# VESC_KS75600_motor_mcu.net
KiCad netlist of a schematic drawn in Altium Designer
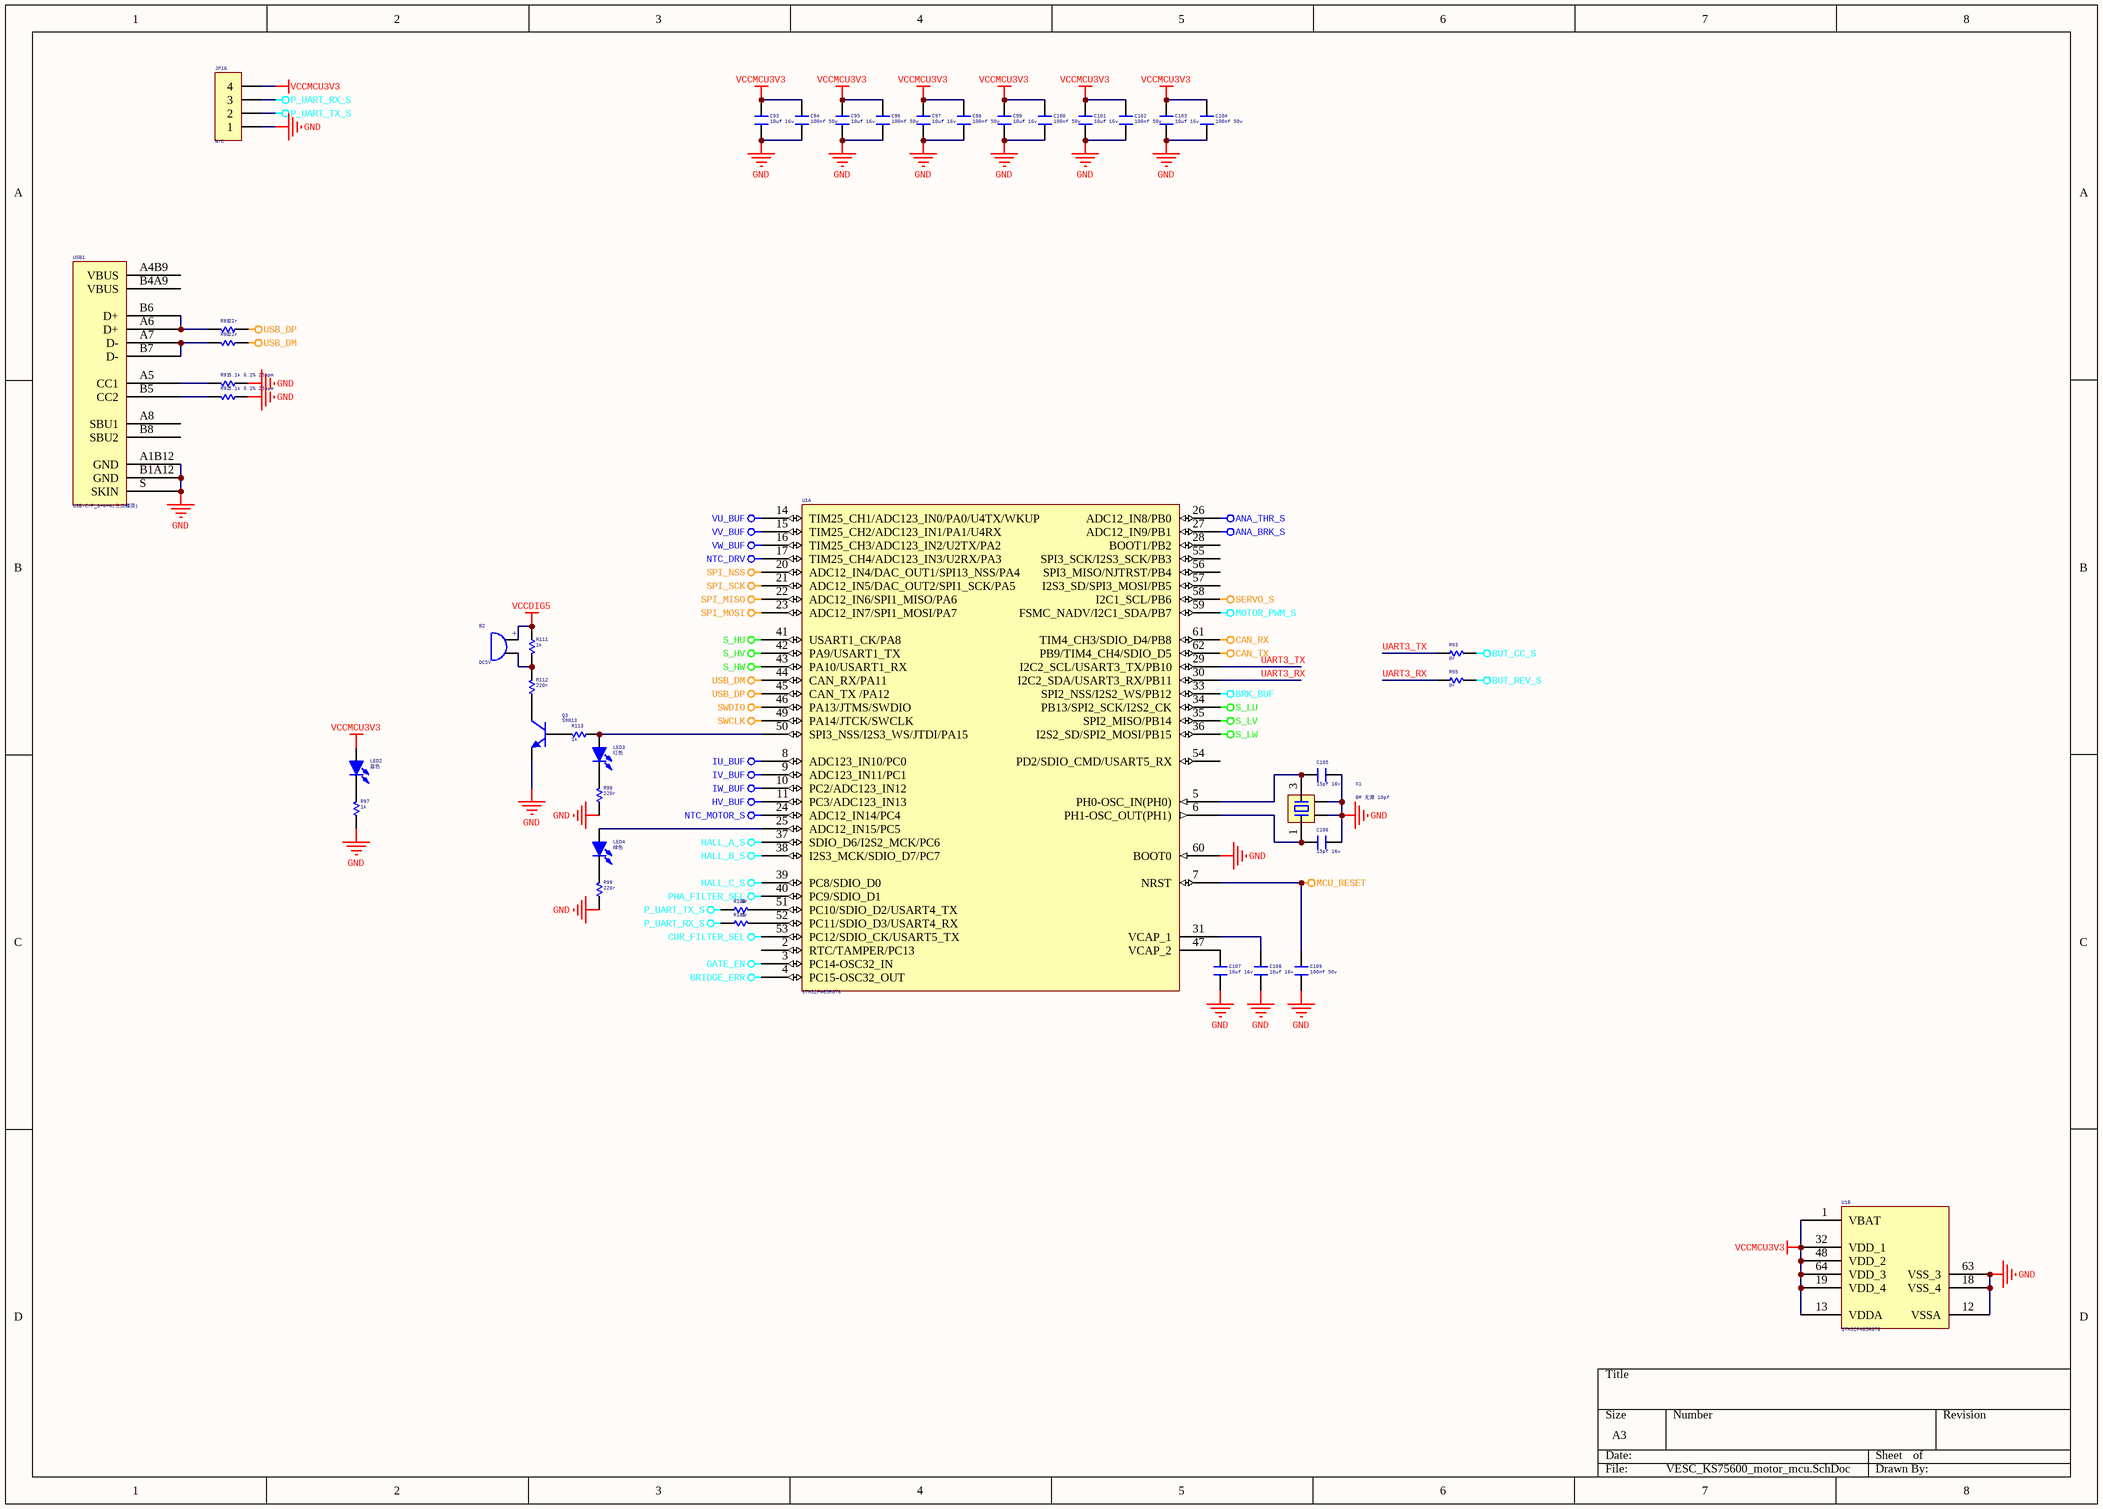
[diagram p0: VESC_KS75600_motor_mcu.SchDoc]

(export (version "E")
  (design (tool "Eeschema 10.0.6"))
  (components
    (comp (ref "B2")
      (value "DC5V")
      (footprint "BEEP 5x9x5.5")
      (description "蜂鸣器")
      (libsource (lib "未分类器件") (part "BEEP"))
    )
    (comp (ref "C93")
      (value "10uf 16v")
      (footprint "C 0805")
      (description "无极性贴片电容")
      (fields (field (name "VOLTAGE") "16v"))
      (libsource (lib "电阻-电容-电感") (part "C"))
    )
    (comp (ref "C94")
      (value "100nf 50v")
      (footprint "C 0603")
      (description "无极性贴片电容")
      (fields (field (name "VOLTAGE") "50v"))
      (libsource (lib "电阻-电容-电感") (part "C"))
    )
    (comp (ref "C95")
      (value "10uf 16v")
      (footprint "C 0805")
      (description "无极性贴片电容")
      (fields (field (name "VOLTAGE") "16v"))
      (libsource (lib "电阻-电容-电感") (part "C"))
    )
    (comp (ref "C96")
      (value "100nf 50v")
      (footprint "C 0603")
      (description "无极性贴片电容")
      (fields (field (name "VOLTAGE") "50v"))
      (libsource (lib "电阻-电容-电感") (part "C"))
    )
    (comp (ref "C97")
      (value "10uf 16v")
      (footprint "C 0805")
      (description "无极性贴片电容")
      (fields (field (name "VOLTAGE") "16v"))
      (libsource (lib "电阻-电容-电感") (part "C"))
    )
    (comp (ref "C98")
      (value "100nf 50v")
      (footprint "C 0603")
      (description "无极性贴片电容")
      (fields (field (name "VOLTAGE") "50v"))
      (libsource (lib "电阻-电容-电感") (part "C"))
    )
    (comp (ref "C99")
      (value "10uf 16v")
      (footprint "C 0805")
      (description "无极性贴片电容")
      (fields (field (name "VOLTAGE") "16v"))
      (libsource (lib "电阻-电容-电感") (part "C"))
    )
    (comp (ref "C100")
      (value "100nf 50v")
      (footprint "C 0603")
      (description "无极性贴片电容")
      (fields (field (name "VOLTAGE") "50v"))
      (libsource (lib "电阻-电容-电感") (part "C"))
    )
    (comp (ref "C101")
      (value "10uf 16v")
      (footprint "C 0805")
      (description "无极性贴片电容")
      (fields (field (name "VOLTAGE") "16v"))
      (libsource (lib "电阻-电容-电感") (part "C"))
    )
    (comp (ref "C102")
      (value "100nf 50v")
      (footprint "C 0603")
      (description "无极性贴片电容")
      (fields (field (name "VOLTAGE") "50v"))
      (libsource (lib "电阻-电容-电感") (part "C"))
    )
    (comp (ref "C103")
      (value "10uf 16v")
      (footprint "C 0805")
      (description "无极性贴片电容")
      (fields (field (name "VOLTAGE") "16v"))
      (libsource (lib "电阻-电容-电感") (part "C"))
    )
    (comp (ref "C104")
      (value "100nf 50v")
      (footprint "C 0603")
      (description "无极性贴片电容")
      (fields (field (name "VOLTAGE") "50v"))
      (libsource (lib "电阻-电容-电感") (part "C"))
    )
    (comp (ref "C105")
      (value "15pf 16v")
      (footprint "C 0603")
      (description "无极性贴片电容")
      (fields (field (name "VOLTAGE") "16v"))
      (libsource (lib "电阻-电容-电感") (part "C"))
    )
    (comp (ref "C106")
      (value "15pf 16v")
      (footprint "C 0603")
      (description "无极性贴片电容")
      (fields (field (name "VOLTAGE") "16v"))
      (libsource (lib "电阻-电容-电感") (part "C"))
    )
    (comp (ref "C107")
      (value "10uf 16v")
      (footprint "C 0805")
      (description "无极性贴片电容")
      (fields (field (name "VOLTAGE") "16v"))
      (libsource (lib "电阻-电容-电感") (part "C"))
    )
    (comp (ref "C108")
      (value "10uf 16v")
      (footprint "C 0805")
      (description "无极性贴片电容")
      (fields (field (name "VOLTAGE") "16v"))
      (libsource (lib "电阻-电容-电感") (part "C"))
    )
    (comp (ref "C109")
      (value "100nf 50v")
      (footprint "C 0603")
      (description "无极性贴片电容")
      (fields (field (name "VOLTAGE") "50v"))
      (libsource (lib "电阻-电容-电感") (part "C"))
    )
    (comp (ref "JP16")
      (value "N/C")
      (footprint "HDR-1X4")
      (description "4P接插件")
      (libsource (lib "接插件") (part "Header 4"))
    )
    (comp (ref "LED2")
      (value "蓝色")
      (footprint "LED 0603G")
      (description "贴片LED")
      (libsource (lib "LED") (part "LED-SMD"))
    )
    (comp (ref "LED3")
      (value "红色")
      (footprint "LED 0603G")
      (description "贴片LED")
      (libsource (lib "LED") (part "LED-SMD"))
    )
    (comp (ref "LED4")
      (value "绿色")
      (footprint "LED 0603G")
      (description "贴片LED")
      (libsource (lib "LED") (part "LED-SMD"))
    )
    (comp (ref "Q3")
      (value "S9013")
      (footprint "SOT23-3N")
      (description "低频放大-NPN型")
      (libsource (lib "三极管") (part "9013-SMD"))
    )
    (comp (ref "R89")
      (value "22r")
      (footprint "R 0603")
      (description "贴片电阻")
      (libsource (lib "电阻-电容-电感") (part "R"))
    )
    (comp (ref "R90")
      (value "22r")
      (footprint "R 0603")
      (description "贴片电阻")
      (libsource (lib "电阻-电容-电感") (part "R"))
    )
    (comp (ref "R91")
      (value "5.1k 0.1% 25ppm")
      (footprint "R 0805-HP")
      (description "贴片电阻")
      (libsource (lib "电阻-电容-电感") (part "R"))
    )
    (comp (ref "R92")
      (value "5.1k 0.1% 25ppm")
      (footprint "R 0805-HP")
      (description "贴片电阻")
      (libsource (lib "电阻-电容-电感") (part "R"))
    )
    (comp (ref "R93")
      (value "0r")
      (footprint "R 0603")
      (description "贴片电阻")
      (libsource (lib "电阻-电容-电感") (part "R"))
    )
    (comp (ref "R95")
      (value "0r")
      (footprint "R 0603")
      (description "贴片电阻")
      (libsource (lib "电阻-电容-电感") (part "R"))
    )
    (comp (ref "R97")
      (value "1k")
      (footprint "R 0603")
      (description "贴片电阻")
      (libsource (lib "电阻-电容-电感") (part "R"))
    )
    (comp (ref "R98")
      (value "220r")
      (footprint "R 0603")
      (description "贴片电阻")
      (libsource (lib "电阻-电容-电感") (part "R"))
    )
    (comp (ref "R99")
      (value "220r")
      (footprint "R 0603")
      (description "贴片电阻")
      (libsource (lib "电阻-电容-电感") (part "R"))
    )
    (comp (ref "R100")
      (value "0r")
      (footprint "R 0603")
      (description "贴片电阻")
      (libsource (lib "电阻-电容-电感") (part "R"))
    )
    (comp (ref "R101")
      (value "0r")
      (footprint "R 0603")
      (description "贴片电阻")
      (libsource (lib "电阻-电容-电感") (part "R"))
    )
    (comp (ref "R111")
      (value "1k")
      (footprint "R 0603")
      (description "贴片电阻")
      (libsource (lib "电阻-电容-电感") (part "R"))
    )
    (comp (ref "R112")
      (value "220r")
      (footprint "R 0603")
      (description "贴片电阻")
      (libsource (lib "电阻-电容-电感") (part "R"))
    )
    (comp (ref "R113")
      (value "1k")
      (footprint "R 0603")
      (description "贴片电阻")
      (libsource (lib "电阻-电容-电感") (part "R"))
    )
    (comp (ref "U1")
      (value "STM32F405RGT6")
      (footprint "LQFP64 10x10_L")
      (description "Flash:1024/RAM:192/IO:51")
      (libsource (lib "STM32系列单片机") (part "STM32F405RG"))
    )
    (comp (ref "USB1")
      (value "USB-C/P_8+4+4(三次模顶)")
      (footprint "USB-C/S_16_0D_F")
      (description "USB-C型贴片母接口 8（8线）+4 (电源) + 4（外壳）（2.0基础数据+CC+SBU）")
      (libsource (lib "接口类") (part "USB-C/P_8+4+4"))
    )
    (comp (ref "X1")
      (value "8M 无源 10pf")
      (footprint "XTAL-3225")
      (description "4脚晶振")
      (libsource (lib "保险丝-晶振") (part "XTAL-4"))
    )
  )
  (nets
    (net (code "1") (name "/UART3_RX") (class "Default")
      (node (ref "R95") (pin "1") (pinfunction "1_1") (pintype "passive"))
      (node (ref "U1") (pin "30") (pinfunction "I2C2_SDA/USART3_RX/PB11_30") (pintype "bidirectional"))
    )
    (net (code "2") (name "/UART3_TX") (class "Default")
      (node (ref "R93") (pin "1") (pinfunction "1_1") (pintype "passive"))
      (node (ref "U1") (pin "29") (pinfunction "I2C2_SCL/USART3_TX/PB10_29") (pintype "bidirectional"))
    )
    (net (code "3") (name "ANA_BRK_S") (class "Default")
      (node (ref "U1") (pin "27") (pinfunction "ADC12_IN9/PB1_27") (pintype "bidirectional"))
    )
    (net (code "4") (name "ANA_THR_S") (class "Default")
      (node (ref "U1") (pin "26") (pinfunction "ADC12_IN8/PB0_26") (pintype "bidirectional"))
    )
    (net (code "5") (name "BRIDGE_ERR") (class "Default")
      (node (ref "U1") (pin "4") (pinfunction "PC15-OSC32_OUT_4") (pintype "bidirectional"))
    )
    (net (code "6") (name "BRK_BUF") (class "Default")
      (node (ref "U1") (pin "33") (pinfunction "SPI2_NSS/I2S2_WS/PB12_33") (pintype "bidirectional"))
    )
    (net (code "7") (name "BUT_CC_S") (class "Default")
      (node (ref "R93") (pin "2") (pinfunction "2_2") (pintype "passive"))
    )
    (net (code "8") (name "BUT_REV_S") (class "Default")
      (node (ref "R95") (pin "2") (pinfunction "2_2") (pintype "passive"))
    )
    (net (code "9") (name "CAN_RX") (class "Default")
      (node (ref "U1") (pin "61") (pinfunction "TIM4_CH3/SDIO_D4/PB8_61") (pintype "bidirectional"))
    )
    (net (code "10") (name "CAN_TX") (class "Default")
      (node (ref "U1") (pin "62") (pinfunction "PB9/TIM4_CH4/SDIO_D5_62") (pintype "bidirectional"))
    )
    (net (code "11") (name "CUR_FILTER_SEL") (class "Default")
      (node (ref "U1") (pin "53") (pinfunction "PC12/SDIO_CK/USART5_TX_53") (pintype "bidirectional"))
    )
    (net (code "12") (name "GATE_EN") (class "Default")
      (node (ref "U1") (pin "3") (pinfunction "PC14-OSC32_IN_3") (pintype "bidirectional"))
    )
    (net (code "13") (name "GND") (class "Default")
      (node (ref "C100") (pin "2") (pinfunction "2_2") (pintype "passive"))
      (node (ref "C101") (pin "2") (pinfunction "2_2") (pintype "passive"))
      (node (ref "C102") (pin "2") (pinfunction "2_2") (pintype "passive"))
      (node (ref "C103") (pin "2") (pinfunction "2_2") (pintype "passive"))
      (node (ref "C104") (pin "2") (pinfunction "2_2") (pintype "passive"))
      (node (ref "C105") (pin "1") (pinfunction "1_1") (pintype "passive"))
      (node (ref "C106") (pin "1") (pinfunction "1_1") (pintype "passive"))
      (node (ref "C107") (pin "2") (pinfunction "2_2") (pintype "passive"))
      (node (ref "C108") (pin "2") (pinfunction "2_2") (pintype "passive"))
      (node (ref "C109") (pin "1") (pinfunction "1_1") (pintype "passive"))
      (node (ref "C93") (pin "2") (pinfunction "2_2") (pintype "passive"))
      (node (ref "C94") (pin "2") (pinfunction "2_2") (pintype "passive"))
      (node (ref "C95") (pin "2") (pinfunction "2_2") (pintype "passive"))
      (node (ref "C96") (pin "2") (pinfunction "2_2") (pintype "passive"))
      (node (ref "C97") (pin "2") (pinfunction "2_2") (pintype "passive"))
      (node (ref "C98") (pin "2") (pinfunction "2_2") (pintype "passive"))
      (node (ref "C99") (pin "2") (pinfunction "2_2") (pintype "passive"))
      (node (ref "JP16") (pin "1") (pinfunction "1_1") (pintype "passive"))
      (node (ref "Q3") (pin "2") (pinfunction "E_2") (pintype "passive"))
      (node (ref "R91") (pin "1") (pinfunction "1_1") (pintype "passive"))
      (node (ref "R92") (pin "1") (pinfunction "1_1") (pintype "passive"))
      (node (ref "R97") (pin "1") (pinfunction "1_1") (pintype "passive"))
      (node (ref "R98") (pin "1") (pinfunction "1_1") (pintype "passive"))
      (node (ref "R99") (pin "1") (pinfunction "1_1") (pintype "passive"))
      (node (ref "U1") (pin "12") (pinfunction "VSSA_12") (pintype "power_in"))
      (node (ref "U1") (pin "18") (pinfunction "VSS_4_18") (pintype "power_in"))
      (node (ref "U1") (pin "60") (pinfunction "BOOT0_60") (pintype "input"))
      (node (ref "U1") (pin "63") (pinfunction "VSS_3_63") (pintype "power_in"))
      (node (ref "USB1") (pin "A1B12") (pinfunction "GND_A1B12") (pintype "passive"))
      (node (ref "USB1") (pin "B1A12") (pinfunction "GND_B1A12") (pintype "passive"))
      (node (ref "USB1") (pin "S") (pinfunction "SKIN_S") (pintype "passive"))
      (node (ref "X1") (pin "2") (pinfunction "2_2") (pintype "passive"))
      (node (ref "X1") (pin "4") (pinfunction "4_4") (pintype "passive"))
    )
    (net (code "14") (name "HALL_A_S") (class "Default")
      (node (ref "U1") (pin "37") (pinfunction "SDIO_D6/I2S2_MCK/PC6_37") (pintype "bidirectional"))
    )
    (net (code "15") (name "HALL_B_S") (class "Default")
      (node (ref "U1") (pin "38") (pinfunction "I2S3_MCK/SDIO_D7/PC7_38") (pintype "bidirectional"))
    )
    (net (code "16") (name "HALL_C_S") (class "Default")
      (node (ref "U1") (pin "39") (pinfunction "PC8/SDIO_D0_39") (pintype "bidirectional"))
    )
    (net (code "17") (name "HV_BUF") (class "Default")
      (node (ref "U1") (pin "11") (pinfunction "PC3/ADC123_IN13_11") (pintype "bidirectional"))
    )
    (net (code "18") (name "IU_BUF") (class "Default")
      (node (ref "U1") (pin "8") (pinfunction "ADC123_IN10/PC0_8") (pintype "bidirectional"))
    )
    (net (code "19") (name "IV_BUF") (class "Default")
      (node (ref "U1") (pin "9") (pinfunction "ADC123_IN11/PC1_9") (pintype "bidirectional"))
    )
    (net (code "20") (name "IW_BUF") (class "Default")
      (node (ref "U1") (pin "10") (pinfunction "PC2/ADC123_IN12_10") (pintype "bidirectional"))
    )
    (net (code "21") (name "MCU_RESET") (class "Default")
      (node (ref "C109") (pin "2") (pinfunction "2_2") (pintype "passive"))
      (node (ref "U1") (pin "7") (pinfunction "NRST_7") (pintype "bidirectional"))
    )
    (net (code "22") (name "MOTOR_PWM_S") (class "Default")
      (node (ref "U1") (pin "59") (pinfunction "FSMC_NADV/I2C1_SDA/PB7_59") (pintype "bidirectional"))
    )
    (net (code "23") (name "NTC_DRV") (class "Default")
      (node (ref "U1") (pin "17") (pinfunction "TIM25_CH4/ADC123_IN3/U2RX/PA3_17") (pintype "bidirectional"))
    )
    (net (code "24") (name "NTC_MOTOR_S") (class "Default")
      (node (ref "U1") (pin "24") (pinfunction "ADC12_IN14/PC4_24") (pintype "bidirectional"))
    )
    (net (code "25") (name "Net-(B2-Pad2)") (class "Default")
      (node (ref "B2") (pin "2") (pinfunction "2_2") (pintype "passive"))
      (node (ref "R111") (pin "2") (pinfunction "2_2") (pintype "passive"))
      (node (ref "R112") (pin "2") (pinfunction "2_2") (pintype "passive"))
    )
    (net (code "26") (name "Net-(LED2-K)") (class "Default")
      (node (ref "LED2") (pin "2") (pinfunction "K_2") (pintype "passive"))
      (node (ref "R97") (pin "2") (pinfunction "2_2") (pintype "passive"))
    )
    (net (code "27") (name "Net-(LED3-A)") (class "Default")
      (node (ref "LED3") (pin "1") (pinfunction "A_1") (pintype "passive"))
      (node (ref "R113") (pin "1") (pinfunction "1_1") (pintype "passive"))
      (node (ref "U1") (pin "50") (pinfunction "SPI3_NSS/I2S3_WS/JTDI/PA15_50") (pintype "bidirectional"))
    )
    (net (code "28") (name "Net-(LED3-K)") (class "Default")
      (node (ref "LED3") (pin "2") (pinfunction "K_2") (pintype "passive"))
      (node (ref "R98") (pin "2") (pinfunction "2_2") (pintype "passive"))
    )
    (net (code "29") (name "Net-(LED4-A)") (class "Default")
      (node (ref "LED4") (pin "1") (pinfunction "A_1") (pintype "passive"))
      (node (ref "U1") (pin "25") (pinfunction "ADC12_IN15/PC5_25") (pintype "bidirectional"))
    )
    (net (code "30") (name "Net-(LED4-K)") (class "Default")
      (node (ref "LED4") (pin "2") (pinfunction "K_2") (pintype "passive"))
      (node (ref "R99") (pin "2") (pinfunction "2_2") (pintype "passive"))
    )
    (net (code "31") (name "Net-(Q3-B)") (class "Default")
      (node (ref "Q3") (pin "1") (pinfunction "B_1") (pintype "passive"))
      (node (ref "R113") (pin "2") (pinfunction "2_2") (pintype "passive"))
    )
    (net (code "32") (name "Net-(Q3-C)") (class "Default")
      (node (ref "Q3") (pin "3") (pinfunction "C_3") (pintype "passive"))
      (node (ref "R112") (pin "1") (pinfunction "1_1") (pintype "passive"))
    )
    (net (code "33") (name "Net-(R89-Pad2)") (class "Default")
      (node (ref "R89") (pin "2") (pinfunction "2_2") (pintype "passive"))
      (node (ref "USB1") (pin "A6") (pinfunction "D+_A6") (pintype "passive"))
      (node (ref "USB1") (pin "B6") (pinfunction "D+_B6") (pintype "passive"))
    )
    (net (code "34") (name "Net-(R90-Pad2)") (class "Default")
      (node (ref "R90") (pin "2") (pinfunction "2_2") (pintype "passive"))
      (node (ref "USB1") (pin "A7") (pinfunction "D-_A7") (pintype "passive"))
      (node (ref "USB1") (pin "B7") (pinfunction "D-_B7") (pintype "passive"))
    )
    (net (code "35") (name "Net-(U1A-PC10{slash}SDIO_D2{slash}USART4_TX)") (class "Default")
      (node (ref "R100") (pin "2") (pinfunction "2_2") (pintype "passive"))
      (node (ref "U1") (pin "51") (pinfunction "PC10/SDIO_D2/USART4_TX_51") (pintype "bidirectional"))
    )
    (net (code "36") (name "Net-(U1A-PC11{slash}SDIO_D3{slash}USART4_RX)") (class "Default")
      (node (ref "R101") (pin "2") (pinfunction "2_2") (pintype "passive"))
      (node (ref "U1") (pin "52") (pinfunction "PC11/SDIO_D3/USART4_RX_52") (pintype "bidirectional"))
    )
    (net (code "37") (name "Net-(U1A-PH0-OSC_IN(PH0))") (class "Default")
      (node (ref "C105") (pin "2") (pinfunction "2_2") (pintype "passive"))
      (node (ref "U1") (pin "5") (pinfunction "PH0-OSC_IN(PH0)_5") (pintype "input"))
      (node (ref "X1") (pin "3") (pinfunction "3_3") (pintype "passive"))
    )
    (net (code "38") (name "Net-(U1A-PH1-OSC_OUT(PH1))") (class "Default")
      (node (ref "C106") (pin "2") (pinfunction "2_2") (pintype "passive"))
      (node (ref "U1") (pin "6") (pinfunction "PH1-OSC_OUT(PH1)_6") (pintype "output"))
      (node (ref "X1") (pin "1") (pinfunction "1_1") (pintype "passive"))
    )
    (net (code "39") (name "Net-(U1A-VCAP_1)") (class "Default")
      (node (ref "C108") (pin "1") (pinfunction "1_1") (pintype "passive"))
      (node (ref "U1") (pin "31") (pinfunction "VCAP_1_31") (pintype "passive"))
    )
    (net (code "40") (name "Net-(U1A-VCAP_2)") (class "Default")
      (node (ref "C107") (pin "1") (pinfunction "1_1") (pintype "passive"))
      (node (ref "U1") (pin "47") (pinfunction "VCAP_2_47") (pintype "passive"))
    )
    (net (code "41") (name "Net-(USB1-CC1)") (class "Default")
      (node (ref "R91") (pin "2") (pinfunction "2_2") (pintype "passive"))
      (node (ref "USB1") (pin "A5") (pinfunction "CC1_A5") (pintype "passive"))
    )
    (net (code "42") (name "Net-(USB1-CC2)") (class "Default")
      (node (ref "R92") (pin "2") (pinfunction "2_2") (pintype "passive"))
      (node (ref "USB1") (pin "B5") (pinfunction "CC2_B5") (pintype "passive"))
    )
    (net (code "43") (name "PHA_FILTER_SEL") (class "Default")
      (node (ref "U1") (pin "40") (pinfunction "PC9/SDIO_D1_40") (pintype "bidirectional"))
    )
    (net (code "44") (name "P_UART_RX_S") (class "Default")
      (node (ref "JP16") (pin "3") (pinfunction "3_3") (pintype "passive"))
      (node (ref "R101") (pin "1") (pinfunction "1_1") (pintype "passive"))
    )
    (net (code "45") (name "P_UART_TX_S") (class "Default")
      (node (ref "JP16") (pin "2") (pinfunction "2_2") (pintype "passive"))
      (node (ref "R100") (pin "1") (pinfunction "1_1") (pintype "passive"))
    )
    (net (code "46") (name "SERVO_S") (class "Default")
      (node (ref "U1") (pin "58") (pinfunction "I2C1_SCL/PB6_58") (pintype "bidirectional"))
    )
    (net (code "47") (name "SPI_MISO") (class "Default")
      (node (ref "U1") (pin "22") (pinfunction "ADC12_IN6/SPI1_MISO/PA6_22") (pintype "bidirectional"))
    )
    (net (code "48") (name "SPI_MOSI") (class "Default")
      (node (ref "U1") (pin "23") (pinfunction "ADC12_IN7/SPI1_MOSI/PA7_23") (pintype "bidirectional"))
    )
    (net (code "49") (name "SPI_NSS") (class "Default")
      (node (ref "U1") (pin "20") (pinfunction "ADC12_IN4/DAC_OUT1/SPI13_NSS/PA4_20") (pintype "bidirectional"))
    )
    (net (code "50") (name "SPI_SCK") (class "Default")
      (node (ref "U1") (pin "21") (pinfunction "ADC12_IN5/DAC_OUT2/SPI1_SCK/PA5_21") (pintype "bidirectional"))
    )
    (net (code "51") (name "SWCLK") (class "Default")
      (node (ref "U1") (pin "49") (pinfunction "PA14/JTCK/SWCLK_49") (pintype "bidirectional"))
    )
    (net (code "52") (name "SWDIO") (class "Default")
      (node (ref "U1") (pin "46") (pinfunction "PA13/JTMS/SWDIO_46") (pintype "bidirectional"))
    )
    (net (code "53") (name "S_HU") (class "Default")
      (node (ref "U1") (pin "41") (pinfunction "USART1_CK/PA8_41") (pintype "bidirectional"))
    )
    (net (code "54") (name "S_HV") (class "Default")
      (node (ref "U1") (pin "42") (pinfunction "PA9/USART1_TX_42") (pintype "bidirectional"))
    )
    (net (code "55") (name "S_HW") (class "Default")
      (node (ref "U1") (pin "43") (pinfunction "PA10/USART1_RX_43") (pintype "bidirectional"))
    )
    (net (code "56") (name "S_LU") (class "Default")
      (node (ref "U1") (pin "34") (pinfunction "PB13/SPI2_SCK/I2S2_CK_34") (pintype "bidirectional"))
    )
    (net (code "57") (name "S_LV") (class "Default")
      (node (ref "U1") (pin "35") (pinfunction "SPI2_MISO/PB14_35") (pintype "bidirectional"))
    )
    (net (code "58") (name "S_LW") (class "Default")
      (node (ref "U1") (pin "36") (pinfunction "I2S2_SD/SPI2_MOSI/PB15_36") (pintype "bidirectional"))
    )
    (net (code "59") (name "USB_DM") (class "Default")
      (node (ref "R90") (pin "1") (pinfunction "1_1") (pintype "passive"))
      (node (ref "U1") (pin "44") (pinfunction "CAN_RX/PA11_44") (pintype "bidirectional"))
    )
    (net (code "60") (name "USB_DP") (class "Default")
      (node (ref "R89") (pin "1") (pinfunction "1_1") (pintype "passive"))
      (node (ref "U1") (pin "45") (pinfunction "CAN_TX_/PA12_45") (pintype "bidirectional"))
    )
    (net (code "61") (name "VCCDIG5") (class "Default")
      (node (ref "B2") (pin "1") (pinfunction "1_1") (pintype "passive"))
      (node (ref "R111") (pin "1") (pinfunction "1_1") (pintype "passive"))
    )
    (net (code "62") (name "VCCMCU3V3") (class "Default")
      (node (ref "C100") (pin "1") (pinfunction "1_1") (pintype "passive"))
      (node (ref "C101") (pin "1") (pinfunction "1_1") (pintype "passive"))
      (node (ref "C102") (pin "1") (pinfunction "1_1") (pintype "passive"))
      (node (ref "C103") (pin "1") (pinfunction "1_1") (pintype "passive"))
      (node (ref "C104") (pin "1") (pinfunction "1_1") (pintype "passive"))
      (node (ref "C93") (pin "1") (pinfunction "1_1") (pintype "passive"))
      (node (ref "C94") (pin "1") (pinfunction "1_1") (pintype "passive"))
      (node (ref "C95") (pin "1") (pinfunction "1_1") (pintype "passive"))
      (node (ref "C96") (pin "1") (pinfunction "1_1") (pintype "passive"))
      (node (ref "C97") (pin "1") (pinfunction "1_1") (pintype "passive"))
      (node (ref "C98") (pin "1") (pinfunction "1_1") (pintype "passive"))
      (node (ref "C99") (pin "1") (pinfunction "1_1") (pintype "passive"))
      (node (ref "JP16") (pin "4") (pinfunction "4_4") (pintype "passive"))
      (node (ref "LED2") (pin "1") (pinfunction "A_1") (pintype "passive"))
      (node (ref "U1") (pin "1") (pinfunction "VBAT_1") (pintype "power_in"))
      (node (ref "U1") (pin "13") (pinfunction "VDDA_13") (pintype "power_in"))
      (node (ref "U1") (pin "19") (pinfunction "VDD_4_19") (pintype "power_in"))
      (node (ref "U1") (pin "32") (pinfunction "VDD_1_32") (pintype "power_in"))
      (node (ref "U1") (pin "48") (pinfunction "VDD_2_48") (pintype "power_in"))
      (node (ref "U1") (pin "64") (pinfunction "VDD_3_64") (pintype "power_in"))
    )
    (net (code "63") (name "VU_BUF") (class "Default")
      (node (ref "U1") (pin "14") (pinfunction "TIM25_CH1/ADC123_IN0/PA0/U4TX/WKUP_14") (pintype "bidirectional"))
    )
    (net (code "64") (name "VV_BUF") (class "Default")
      (node (ref "U1") (pin "15") (pinfunction "TIM25_CH2/ADC123_IN1/PA1/U4RX_15") (pintype "bidirectional"))
    )
    (net (code "65") (name "VW_BUF") (class "Default")
      (node (ref "U1") (pin "16") (pinfunction "TIM25_CH3/ADC123_IN2/U2TX/PA2_16") (pintype "bidirectional"))
    )
    (net (code "66") (name "unconnected-(U1A-BOOT1{slash}PB2-Pad28)") (class "Default")
      (node (ref "U1") (pin "28") (pinfunction "BOOT1/PB2_28") (pintype "bidirectional"))
    )
    (net (code "67") (name "unconnected-(U1A-I2S3_SD{slash}SPI3_MOSI{slash}PB5-Pad57)") (class "Default")
      (node (ref "U1") (pin "57") (pinfunction "I2S3_SD/SPI3_MOSI/PB5_57") (pintype "bidirectional"))
    )
    (net (code "68") (name "unconnected-(U1A-PD2{slash}SDIO_CMD{slash}USART5_RX-Pad54)") (class "Default")
      (node (ref "U1") (pin "54") (pinfunction "PD2/SDIO_CMD/USART5_RX_54") (pintype "bidirectional"))
    )
    (net (code "69") (name "unconnected-(U1A-RTC{slash}TAMPER{slash}PC13-Pad2)") (class "Default")
      (node (ref "U1") (pin "2") (pinfunction "RTC/TAMPER/PC13_2") (pintype "bidirectional"))
    )
    (net (code "70") (name "unconnected-(U1A-SPI3_MISO{slash}NJTRST{slash}PB4-Pad56)") (class "Default")
      (node (ref "U1") (pin "56") (pinfunction "SPI3_MISO/NJTRST/PB4_56") (pintype "bidirectional"))
    )
    (net (code "71") (name "unconnected-(U1A-SPI3_SCK{slash}I2S3_SCK{slash}PB3-Pad55)") (class "Default")
      (node (ref "U1") (pin "55") (pinfunction "SPI3_SCK/I2S3_SCK/PB3_55") (pintype "bidirectional"))
    )
    (net (code "72") (name "unconnected-(USB1-SBU1-PadA8)") (class "Default")
      (node (ref "USB1") (pin "A8") (pinfunction "SBU1_A8") (pintype "passive"))
    )
    (net (code "73") (name "unconnected-(USB1-SBU2-PadB8)") (class "Default")
      (node (ref "USB1") (pin "B8") (pinfunction "SBU2_B8") (pintype "passive"))
    )
    (net (code "74") (name "unconnected-(USB1-VBUS-PadA4B9)") (class "Default")
      (node (ref "USB1") (pin "A4B9") (pinfunction "VBUS_A4B9") (pintype "passive"))
    )
    (net (code "75") (name "unconnected-(USB1-VBUS-PadB4A9)") (class "Default")
      (node (ref "USB1") (pin "B4A9") (pinfunction "VBUS_B4A9") (pintype "passive"))
    )
  )
)
